# GSM_Based_Irrigation.net
KiCad netlist of a schematic drawn in EAGLE
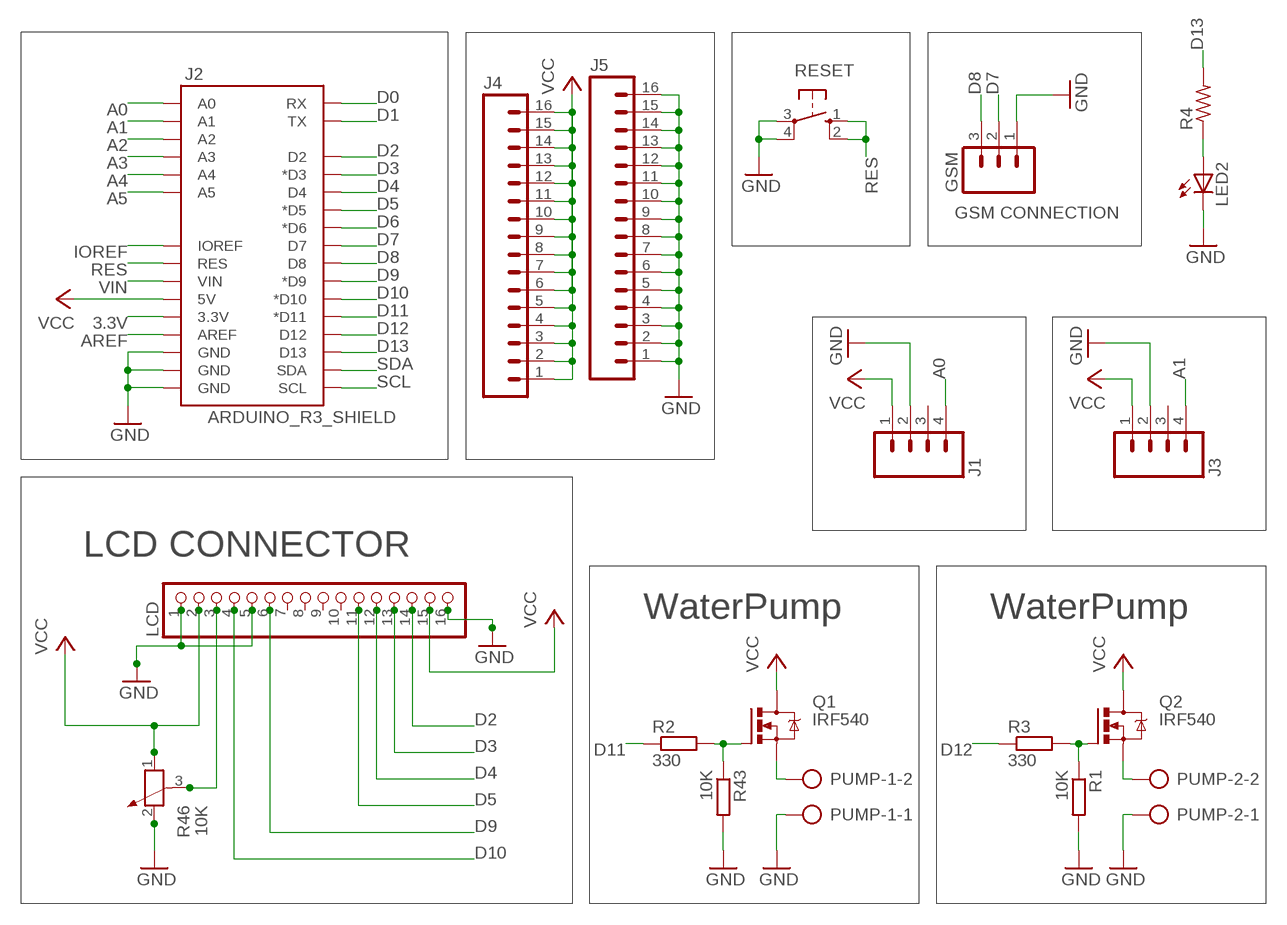
[diagram p0: schematic, sheet 1]

(export (version "E")
  (design (tool "Eeschema 10.0.6"))
  (components
    (comp (ref "GSM")
      (value "M03LONGPADS")
      (footprint "eagle-import:1X03_LONGPADS")
      (libsource (lib "eagle-import") (part "M03LONGPADS"))
    )
    (comp (ref "J1")
      (value "M04LONGPADS")
      (footprint "eagle-import:1X04_LONGPADS")
      (libsource (lib "eagle-import") (part "M04LONGPADS"))
    )
    (comp (ref "J2")
      (value "ARDUINO_R3_SHIELD")
      (footprint "eagle-import:UNO_R3_SHIELD")
      (libsource (lib "eagle-import") (part "ARDUINO_R3_SHIELD"))
    )
    (comp (ref "J3")
      (value "M04LONGPADS")
      (footprint "eagle-import:1X04_LONGPADS")
      (libsource (lib "eagle-import") (part "M04LONGPADS"))
    )
    (comp (ref "J4")
      (value "M16LONGPADS")
      (footprint "eagle-import:1X16_LONGPADS")
      (libsource (lib "eagle-import") (part "M16LONGPADS"))
    )
    (comp (ref "J5")
      (value "M16LONGPADS")
      (footprint "eagle-import:1X16_LONGPADS")
      (libsource (lib "eagle-import") (part "M16LONGPADS"))
    )
    (comp (ref "LCD")
      (value "PINHD-1X16")
      (footprint "eagle-import:1X16")
      (libsource (lib "eagle-import") (part "PINHD-1X16"))
    )
    (comp (ref "LED2")
      (value "LED5MM")
      (footprint "eagle-import:LED5MM")
      (libsource (lib "eagle-import") (part "LED5MM"))
    )
    (comp (ref "PUMP-1")
      (value "AK300/2")
      (footprint "eagle-import:AK300_2")
      (libsource (lib "eagle-import") (part "AK300/2"))
    )
    (comp (ref "PUMP-2")
      (value "AK300/2")
      (footprint "eagle-import:AK300_2")
      (libsource (lib "eagle-import") (part "AK300/2"))
    )
    (comp (ref "Q1")
      (value "IRF540")
      (footprint "eagle-import:TO220BV")
      (libsource (lib "eagle-import") (part "IRF540"))
    )
    (comp (ref "Q2")
      (value "IRF540")
      (footprint "eagle-import:TO220BV")
      (libsource (lib "eagle-import") (part "IRF540"))
    )
    (comp (ref "R1")
      (value "10K")
      (footprint "eagle-import:0207_7@1")
      (libsource (lib "eagle-import") (part "R-EU_0207/7"))
    )
    (comp (ref "R2")
      (value "330")
      (footprint "eagle-import:0207_7@1")
      (libsource (lib "eagle-import") (part "R-EU_0207/7"))
    )
    (comp (ref "R3")
      (value "330")
      (footprint "eagle-import:0207_7@1")
      (libsource (lib "eagle-import") (part "R-EU_0207/7"))
    )
    (comp (ref "R4")
      (value "R-US_0207/10")
      (footprint "eagle-import:0207_10")
      (libsource (lib "eagle-import") (part "R-US_0207/10"))
    )
    (comp (ref "R43")
      (value "10K")
      (footprint "eagle-import:0207_7@1")
      (libsource (lib "eagle-import") (part "R-EU_0207/7"))
    )
    (comp (ref "R46")
      (value "10K")
      (footprint "eagle-import:PT-10")
      (libsource (lib "eagle-import") (part "POTENTIOMETER_PT-10"))
    )
    (comp (ref "RESET")
      (value "10-XX")
      (footprint "eagle-import:B3F-10XX")
      (fields (field (name "MPN") "B3F-1000"))
      (libsource (lib "eagle-import") (part "10-XX"))
    )
  )
  (nets
    (net (code "1") (name "/3.3V") (class "Default")
      (node (ref "J2") (pin "3.3V") (pinfunction "3.3V_3.3V") (pintype "bidirectional"))
    )
    (net (code "2") (name "/A0") (class "Default")
      (node (ref "J1") (pin "4") (pinfunction "4_4") (pintype "passive"))
      (node (ref "J2") (pin "A0") (pinfunction "A0_A0") (pintype "bidirectional"))
    )
    (net (code "3") (name "/A1") (class "Default")
      (node (ref "J2") (pin "A1") (pinfunction "A1_A1") (pintype "bidirectional"))
      (node (ref "J3") (pin "4") (pinfunction "4_4") (pintype "passive"))
    )
    (net (code "4") (name "/A2") (class "Default")
      (node (ref "J2") (pin "A2") (pinfunction "A2_A2") (pintype "bidirectional"))
    )
    (net (code "5") (name "/A3") (class "Default")
      (node (ref "J2") (pin "A3") (pinfunction "A3_A3") (pintype "bidirectional"))
    )
    (net (code "6") (name "/A4") (class "Default")
      (node (ref "J2") (pin "A4") (pinfunction "A4_A4") (pintype "bidirectional"))
    )
    (net (code "7") (name "/A5") (class "Default")
      (node (ref "J2") (pin "A5") (pinfunction "A5_A5") (pintype "bidirectional"))
    )
    (net (code "8") (name "/AREF") (class "Default")
      (node (ref "J2") (pin "AREF") (pinfunction "AREF_AREF") (pintype "bidirectional"))
    )
    (net (code "9") (name "/D0") (class "Default")
      (node (ref "J2") (pin "RX") (pinfunction "RX_RX") (pintype "bidirectional"))
    )
    (net (code "10") (name "/D1") (class "Default")
      (node (ref "J2") (pin "TX") (pinfunction "TX_TX") (pintype "bidirectional"))
    )
    (net (code "11") (name "/D2") (class "Default")
      (node (ref "J2") (pin "D2") (pinfunction "D2_D2") (pintype "bidirectional"))
      (node (ref "LCD") (pin "14") (pinfunction "14_14") (pintype "passive"))
    )
    (net (code "12") (name "/D3") (class "Default")
      (node (ref "J2") (pin "D3") (pinfunction "*D3_D3") (pintype "bidirectional"))
      (node (ref "LCD") (pin "13") (pinfunction "13_13") (pintype "passive"))
    )
    (net (code "13") (name "/D4") (class "Default")
      (node (ref "J2") (pin "D4") (pinfunction "D4_D4") (pintype "bidirectional"))
      (node (ref "LCD") (pin "12") (pinfunction "12_12") (pintype "passive"))
    )
    (net (code "14") (name "/D5") (class "Default")
      (node (ref "J2") (pin "D5") (pinfunction "*D5_D5") (pintype "bidirectional"))
      (node (ref "LCD") (pin "11") (pinfunction "11_11") (pintype "passive"))
    )
    (net (code "15") (name "/D6") (class "Default")
      (node (ref "J2") (pin "D6") (pinfunction "*D6_D6") (pintype "bidirectional"))
    )
    (net (code "16") (name "/D7") (class "Default")
      (node (ref "GSM") (pin "2") (pinfunction "2_2") (pintype "passive"))
      (node (ref "J2") (pin "D7") (pinfunction "D7_D7") (pintype "bidirectional"))
    )
    (net (code "17") (name "/D8") (class "Default")
      (node (ref "GSM") (pin "3") (pinfunction "3_3") (pintype "passive"))
      (node (ref "J2") (pin "D8") (pinfunction "D8_D8") (pintype "bidirectional"))
    )
    (net (code "18") (name "/D9") (class "Default")
      (node (ref "J2") (pin "D9") (pinfunction "*D9_D9") (pintype "bidirectional"))
      (node (ref "LCD") (pin "6") (pinfunction "6_6") (pintype "passive"))
    )
    (net (code "19") (name "/D10") (class "Default")
      (node (ref "J2") (pin "D10") (pinfunction "*D10_D10") (pintype "bidirectional"))
      (node (ref "LCD") (pin "4") (pinfunction "4_4") (pintype "passive"))
    )
    (net (code "20") (name "/D11") (class "Default")
      (node (ref "J2") (pin "D11") (pinfunction "*D11_D11") (pintype "bidirectional"))
      (node (ref "R2") (pin "1") (pinfunction "1_1") (pintype "passive"))
    )
    (net (code "21") (name "/D12") (class "Default")
      (node (ref "J2") (pin "D12") (pinfunction "D12_D12") (pintype "bidirectional"))
      (node (ref "R3") (pin "1") (pinfunction "1_1") (pintype "passive"))
    )
    (net (code "22") (name "/D13") (class "Default")
      (node (ref "J2") (pin "D13") (pinfunction "D13_D13") (pintype "bidirectional"))
      (node (ref "R4") (pin "2") (pinfunction "2_2") (pintype "passive"))
    )
    (net (code "23") (name "/IOREF") (class "Default")
      (node (ref "J2") (pin "IOREF") (pinfunction "IOREF_IOREF") (pintype "bidirectional"))
    )
    (net (code "24") (name "/RES") (class "Default")
      (node (ref "J2") (pin "RES") (pinfunction "RES_RES") (pintype "bidirectional"))
      (node (ref "RESET") (pin "1") (pinfunction "S_1") (pintype "passive"))
      (node (ref "RESET") (pin "2") (pinfunction "S1_2") (pintype "passive"))
    )
    (net (code "25") (name "/SCL") (class "Default")
      (node (ref "J2") (pin "SCL") (pinfunction "SCL_SCL") (pintype "bidirectional"))
    )
    (net (code "26") (name "/SDA") (class "Default")
      (node (ref "J2") (pin "SDA") (pinfunction "SDA_SDA") (pintype "bidirectional"))
    )
    (net (code "27") (name "/VIN") (class "Default")
      (node (ref "J2") (pin "VIN") (pinfunction "VIN_VIN") (pintype "bidirectional"))
    )
    (net (code "28") (name "GND") (class "Default")
      (node (ref "GSM") (pin "1") (pinfunction "1_1") (pintype "passive"))
      (node (ref "J1") (pin "2") (pinfunction "2_2") (pintype "passive"))
      (node (ref "J2") (pin "GND@0") (pinfunction "GND_GND@0") (pintype "bidirectional"))
      (node (ref "J2") (pin "GND@1") (pinfunction "GND_GND@1") (pintype "bidirectional"))
      (node (ref "J2") (pin "GND@2") (pinfunction "GND_GND@2") (pintype "bidirectional"))
      (node (ref "J3") (pin "2") (pinfunction "2_2") (pintype "passive"))
      (node (ref "J5") (pin "1") (pinfunction "1_1") (pintype "passive"))
      (node (ref "J5") (pin "10") (pinfunction "10_10") (pintype "passive"))
      (node (ref "J5") (pin "11") (pinfunction "11_11") (pintype "passive"))
      (node (ref "J5") (pin "12") (pinfunction "12_12") (pintype "passive"))
      (node (ref "J5") (pin "13") (pinfunction "13_13") (pintype "passive"))
      (node (ref "J5") (pin "14") (pinfunction "14_14") (pintype "passive"))
      (node (ref "J5") (pin "15") (pinfunction "15_15") (pintype "passive"))
      (node (ref "J5") (pin "16") (pinfunction "16_16") (pintype "passive"))
      (node (ref "J5") (pin "2") (pinfunction "2_2") (pintype "passive"))
      (node (ref "J5") (pin "3") (pinfunction "3_3") (pintype "passive"))
      (node (ref "J5") (pin "4") (pinfunction "4_4") (pintype "passive"))
      (node (ref "J5") (pin "5") (pinfunction "5_5") (pintype "passive"))
      (node (ref "J5") (pin "6") (pinfunction "6_6") (pintype "passive"))
      (node (ref "J5") (pin "7") (pinfunction "7_7") (pintype "passive"))
      (node (ref "J5") (pin "8") (pinfunction "8_8") (pintype "passive"))
      (node (ref "J5") (pin "9") (pinfunction "9_9") (pintype "passive"))
      (node (ref "LCD") (pin "1") (pinfunction "1_1") (pintype "passive"))
      (node (ref "LCD") (pin "16") (pinfunction "16_16") (pintype "passive"))
      (node (ref "LCD") (pin "5") (pinfunction "5_5") (pintype "passive"))
      (node (ref "LED2") (pin "K") (pinfunction "C_K") (pintype "passive"))
      (node (ref "PUMP-1") (pin "1") (pinfunction "KL_1") (pintype "passive"))
      (node (ref "PUMP-2") (pin "1") (pinfunction "KL_1") (pintype "passive"))
      (node (ref "R1") (pin "2") (pinfunction "2_2") (pintype "passive"))
      (node (ref "R43") (pin "2") (pinfunction "2_2") (pintype "passive"))
      (node (ref "R46") (pin "2") (pinfunction "2_2") (pintype "passive"))
      (node (ref "RESET") (pin "3") (pinfunction "P_3") (pintype "passive"))
      (node (ref "RESET") (pin "4") (pinfunction "P1_4") (pintype "passive"))
    )
    (net (code "29") (name "Net-(LCD-Pad3)") (class "Default")
      (node (ref "LCD") (pin "3") (pinfunction "3_3") (pintype "passive"))
      (node (ref "R46") (pin "3") (pinfunction "3_3") (pintype "passive"))
    )
    (net (code "30") (name "Net-(LED2-PadA)") (class "Default")
      (node (ref "LED2") (pin "A") (pinfunction "A_A") (pintype "passive"))
      (node (ref "R4") (pin "1") (pinfunction "1_1") (pintype "passive"))
    )
    (net (code "31") (name "Net-(PUMP-1B-KL)") (class "Default")
      (node (ref "PUMP-1") (pin "2") (pinfunction "KL_2") (pintype "passive"))
      (node (ref "Q1") (pin "S") (pinfunction "S_S") (pintype "passive"))
    )
    (net (code "32") (name "Net-(PUMP-2B-KL)") (class "Default")
      (node (ref "PUMP-2") (pin "2") (pinfunction "KL_2") (pintype "passive"))
      (node (ref "Q2") (pin "S") (pinfunction "S_S") (pintype "passive"))
    )
    (net (code "33") (name "Net-(Q1-PadG)") (class "Default")
      (node (ref "Q1") (pin "G") (pinfunction "G_G") (pintype "passive"))
      (node (ref "R2") (pin "2") (pinfunction "2_2") (pintype "passive"))
      (node (ref "R43") (pin "1") (pinfunction "1_1") (pintype "passive"))
    )
    (net (code "34") (name "Net-(Q2-PadG)") (class "Default")
      (node (ref "Q2") (pin "G") (pinfunction "G_G") (pintype "passive"))
      (node (ref "R1") (pin "1") (pinfunction "1_1") (pintype "passive"))
      (node (ref "R3") (pin "2") (pinfunction "2_2") (pintype "passive"))
    )
    (net (code "35") (name "VCC") (class "Default")
      (node (ref "J1") (pin "1") (pinfunction "1_1") (pintype "passive"))
      (node (ref "J2") (pin "5V") (pinfunction "5V_5V") (pintype "bidirectional"))
      (node (ref "J3") (pin "1") (pinfunction "1_1") (pintype "passive"))
      (node (ref "J4") (pin "1") (pinfunction "1_1") (pintype "passive"))
      (node (ref "J4") (pin "10") (pinfunction "10_10") (pintype "passive"))
      (node (ref "J4") (pin "11") (pinfunction "11_11") (pintype "passive"))
      (node (ref "J4") (pin "12") (pinfunction "12_12") (pintype "passive"))
      (node (ref "J4") (pin "13") (pinfunction "13_13") (pintype "passive"))
      (node (ref "J4") (pin "14") (pinfunction "14_14") (pintype "passive"))
      (node (ref "J4") (pin "15") (pinfunction "15_15") (pintype "passive"))
      (node (ref "J4") (pin "16") (pinfunction "16_16") (pintype "passive"))
      (node (ref "J4") (pin "2") (pinfunction "2_2") (pintype "passive"))
      (node (ref "J4") (pin "3") (pinfunction "3_3") (pintype "passive"))
      (node (ref "J4") (pin "4") (pinfunction "4_4") (pintype "passive"))
      (node (ref "J4") (pin "5") (pinfunction "5_5") (pintype "passive"))
      (node (ref "J4") (pin "6") (pinfunction "6_6") (pintype "passive"))
      (node (ref "J4") (pin "7") (pinfunction "7_7") (pintype "passive"))
      (node (ref "J4") (pin "8") (pinfunction "8_8") (pintype "passive"))
      (node (ref "J4") (pin "9") (pinfunction "9_9") (pintype "passive"))
      (node (ref "LCD") (pin "15") (pinfunction "15_15") (pintype "passive"))
      (node (ref "LCD") (pin "2") (pinfunction "2_2") (pintype "passive"))
      (node (ref "Q1") (pin "D") (pinfunction "D_D") (pintype "passive"))
      (node (ref "Q2") (pin "D") (pinfunction "D_D") (pintype "passive"))
      (node (ref "R46") (pin "1") (pinfunction "1_1") (pintype "passive"))
    )
    (net (code "36") (name "unconnected-(J1-Pad3)") (class "Default")
      (node (ref "J1") (pin "3") (pinfunction "3_3") (pintype "passive"))
    )
    (net (code "37") (name "unconnected-(J3-Pad3)") (class "Default")
      (node (ref "J3") (pin "3") (pinfunction "3_3") (pintype "passive"))
    )
    (net (code "38") (name "unconnected-(LCD-Pad7)") (class "Default")
      (node (ref "LCD") (pin "7") (pinfunction "7_7") (pintype "passive"))
    )
    (net (code "39") (name "unconnected-(LCD-Pad8)") (class "Default")
      (node (ref "LCD") (pin "8") (pinfunction "8_8") (pintype "passive"))
    )
    (net (code "40") (name "unconnected-(LCD-Pad9)") (class "Default")
      (node (ref "LCD") (pin "9") (pinfunction "9_9") (pintype "passive"))
    )
    (net (code "41") (name "unconnected-(LCD-Pad10)") (class "Default")
      (node (ref "LCD") (pin "10") (pinfunction "10_10") (pintype "passive"))
    )
  )
)
